# daughter-pots2_1.net
KiCad netlist of a schematic drawn in EAGLE
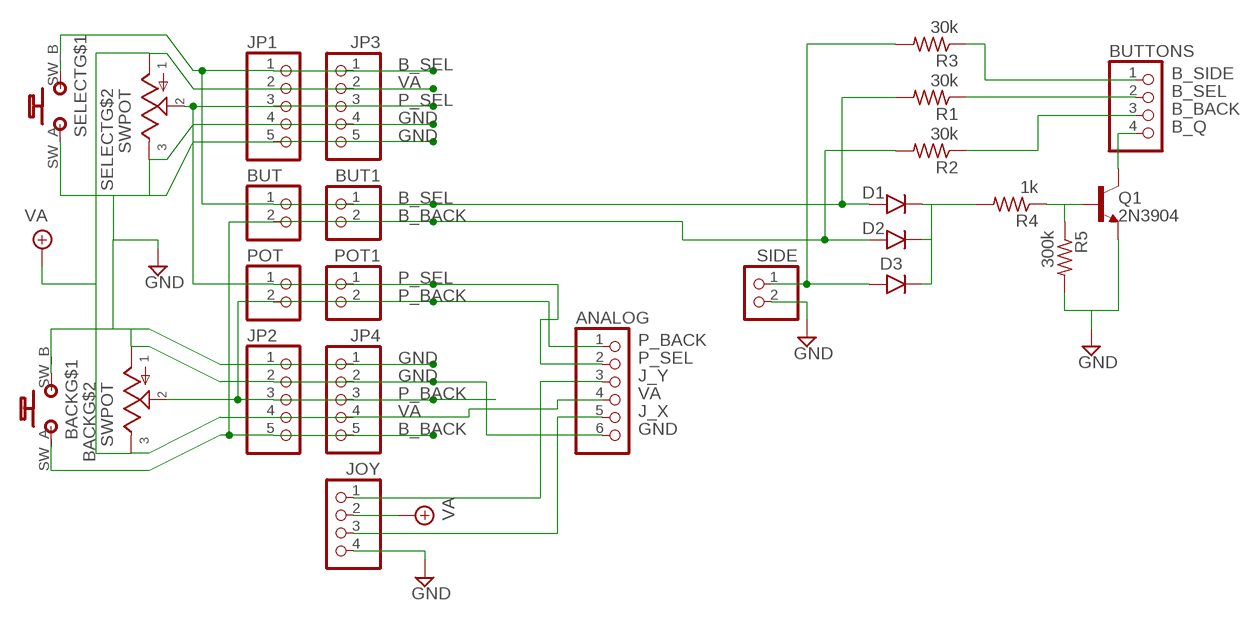
[diagram p0: schematic, sheet 1]

(export (version "E")
  (design (tool "Eeschema 10.0.6"))
  (components
    (comp (ref "ANALOG")
      (value "PINHD-1X6")
      (footprint "eagle-import:1X06")
      (libsource (lib "eagle-import") (part "PINHD-1X6"))
    )
    (comp (ref "BACK")
      (value "SWPOT")
      (footprint "eagle-import:SWPOT")
      (libsource (lib "eagle-import") (part "SWPOT"))
    )
    (comp (ref "BUT")
      (value "PINHD-1X2")
      (footprint "eagle-import:1X02")
      (libsource (lib "eagle-import") (part "PINHD-1X2"))
    )
    (comp (ref "BUT1")
      (value "PINHD-1X2")
      (footprint "eagle-import:1X02")
      (libsource (lib "eagle-import") (part "PINHD-1X2"))
    )
    (comp (ref "BUTTONS")
      (value "PINHD-1X4")
      (footprint "eagle-import:1X04")
      (libsource (lib "eagle-import") (part "PINHD-1X4"))
    )
    (comp (ref "D1")
      (value "1N4148-3")
      (footprint "eagle-import:DO35-3")
      (libsource (lib "eagle-import") (part "1N4148-3"))
    )
    (comp (ref "D2")
      (value "1N4148-2")
      (footprint "eagle-import:DO35-2")
      (libsource (lib "eagle-import") (part "1N4148-2"))
    )
    (comp (ref "D3")
      (value "1N4148-4")
      (footprint "eagle-import:DO35-4")
      (libsource (lib "eagle-import") (part "1N4148-4"))
    )
    (comp (ref "JOY")
      (value "PINHD-1X4")
      (footprint "eagle-import:1X04")
      (libsource (lib "eagle-import") (part "PINHD-1X4"))
    )
    (comp (ref "JP1")
      (value "PINHD-1X5")
      (footprint "eagle-import:1X05")
      (libsource (lib "eagle-import") (part "PINHD-1X5"))
    )
    (comp (ref "JP2")
      (value "PINHD-1X5")
      (footprint "eagle-import:1X05")
      (libsource (lib "eagle-import") (part "PINHD-1X5"))
    )
    (comp (ref "JP3")
      (value "PINHD-1X5")
      (footprint "eagle-import:1X05")
      (libsource (lib "eagle-import") (part "PINHD-1X5"))
    )
    (comp (ref "JP4")
      (value "PINHD-1X5")
      (footprint "eagle-import:1X05")
      (libsource (lib "eagle-import") (part "PINHD-1X5"))
    )
    (comp (ref "POT")
      (value "PINHD-1X2")
      (footprint "eagle-import:1X02")
      (libsource (lib "eagle-import") (part "PINHD-1X2"))
    )
    (comp (ref "POT1")
      (value "PINHD-1X2")
      (footprint "eagle-import:1X02")
      (libsource (lib "eagle-import") (part "PINHD-1X2"))
    )
    (comp (ref "Q1")
      (value "2N3904")
      (footprint "eagle-import:TO92-")
      (libsource (lib "eagle-import") (part "2N3904"))
    )
    (comp (ref "R1")
      (value "30k")
      (footprint "eagle-import:R0207_3")
      (libsource (lib "eagle-import") (part "6MM.3"))
    )
    (comp (ref "R2")
      (value "30k")
      (footprint "eagle-import:R0207_3")
      (libsource (lib "eagle-import") (part "6MM.3"))
    )
    (comp (ref "R3")
      (value "30k")
      (footprint "eagle-import:R0207_3")
      (libsource (lib "eagle-import") (part "6MM.3"))
    )
    (comp (ref "R4")
      (value "1k")
      (footprint "eagle-import:R0207_3")
      (libsource (lib "eagle-import") (part "6MM.3"))
    )
    (comp (ref "R5")
      (value "300k")
      (footprint "eagle-import:R0207_1V")
      (libsource (lib "eagle-import") (part "6MM.1"))
    )
    (comp (ref "SELECT")
      (value "SWPOT")
      (footprint "eagle-import:SWPOT")
      (libsource (lib "eagle-import") (part "SWPOT"))
    )
    (comp (ref "SIDE")
      (value "PINHD-1X2")
      (footprint "eagle-import:1X02")
      (libsource (lib "eagle-import") (part "PINHD-1X2"))
    )
  )
  (nets
    (net (code "1") (name "/B_BACK") (class "Default")
      (node (ref "BACK") (pin "SW_A") (pinfunction "B_A_SW_A") (pintype "passive"))
      (node (ref "BUT") (pin "2") (pinfunction "2_2") (pintype "passive"))
      (node (ref "BUT1") (pin "2") (pinfunction "2_2") (pintype "passive"))
      (node (ref "D2") (pin "A") (pinfunction "A_A") (pintype "passive"))
      (node (ref "JP2") (pin "5") (pinfunction "5_5") (pintype "passive"))
      (node (ref "JP4") (pin "5") (pinfunction "5_5") (pintype "passive"))
      (node (ref "R2") (pin "2") (pinfunction "2_2") (pintype "passive"))
    )
    (net (code "2") (name "/B_Q") (class "Default")
      (node (ref "BUTTONS") (pin "4") (pinfunction "4_4") (pintype "passive"))
      (node (ref "Q1") (pin "1") (pinfunction "C_1") (pintype "passive"))
    )
    (net (code "3") (name "/B_SEL") (class "Default")
      (node (ref "BUT") (pin "1") (pinfunction "1_1") (pintype "passive"))
      (node (ref "BUT1") (pin "1") (pinfunction "1_1") (pintype "passive"))
      (node (ref "D1") (pin "A") (pinfunction "A_A") (pintype "passive"))
      (node (ref "JP1") (pin "1") (pinfunction "1_1") (pintype "passive"))
      (node (ref "JP3") (pin "1") (pinfunction "1_1") (pintype "passive"))
      (node (ref "R1") (pin "2") (pinfunction "2_2") (pintype "passive"))
      (node (ref "SELECT") (pin "SW_B") (pinfunction "B_B_SW_B") (pintype "passive"))
    )
    (net (code "4") (name "/B_SIDE") (class "Default")
      (node (ref "D3") (pin "A") (pinfunction "A_A") (pintype "passive"))
      (node (ref "R3") (pin "2") (pinfunction "2_2") (pintype "passive"))
      (node (ref "SIDE") (pin "1") (pinfunction "1_1") (pintype "passive"))
    )
    (net (code "5") (name "/J_X") (class "Default")
      (node (ref "ANALOG") (pin "5") (pinfunction "5_5") (pintype "passive"))
      (node (ref "JOY") (pin "3") (pinfunction "3_3") (pintype "passive"))
    )
    (net (code "6") (name "/J_Y") (class "Default")
      (node (ref "ANALOG") (pin "3") (pinfunction "3_3") (pintype "passive"))
      (node (ref "JOY") (pin "1") (pinfunction "1_1") (pintype "passive"))
    )
    (net (code "7") (name "/P_BACK") (class "Default")
      (node (ref "ANALOG") (pin "1") (pinfunction "1_1") (pintype "passive"))
      (node (ref "BACK") (pin "POT_W") (pinfunction "POT_W_POT_W") (pintype "passive"))
      (node (ref "JP2") (pin "3") (pinfunction "3_3") (pintype "passive"))
      (node (ref "JP4") (pin "3") (pinfunction "3_3") (pintype "passive"))
      (node (ref "POT") (pin "2") (pinfunction "2_2") (pintype "passive"))
      (node (ref "POT1") (pin "2") (pinfunction "2_2") (pintype "passive"))
    )
    (net (code "8") (name "/P_SEL") (class "Default")
      (node (ref "ANALOG") (pin "2") (pinfunction "2_2") (pintype "passive"))
      (node (ref "JP1") (pin "3") (pinfunction "3_3") (pintype "passive"))
      (node (ref "JP3") (pin "3") (pinfunction "3_3") (pintype "passive"))
      (node (ref "POT") (pin "1") (pinfunction "1_1") (pintype "passive"))
      (node (ref "POT1") (pin "1") (pinfunction "1_1") (pintype "passive"))
      (node (ref "SELECT") (pin "POT_W") (pinfunction "POT_W_POT_W") (pintype "passive"))
    )
    (net (code "9") (name "GND") (class "Default")
      (node (ref "ANALOG") (pin "6") (pinfunction "6_6") (pintype "passive"))
      (node (ref "BACK") (pin "POT_B") (pinfunction "POT_B_POT_B") (pintype "passive"))
      (node (ref "BACK") (pin "SW_B") (pinfunction "B_B_SW_B") (pintype "passive"))
      (node (ref "JOY") (pin "4") (pinfunction "4_4") (pintype "passive"))
      (node (ref "JP1") (pin "4") (pinfunction "4_4") (pintype "passive"))
      (node (ref "JP1") (pin "5") (pinfunction "5_5") (pintype "passive"))
      (node (ref "JP2") (pin "1") (pinfunction "1_1") (pintype "passive"))
      (node (ref "JP2") (pin "2") (pinfunction "2_2") (pintype "passive"))
      (node (ref "JP3") (pin "4") (pinfunction "4_4") (pintype "passive"))
      (node (ref "JP3") (pin "5") (pinfunction "5_5") (pintype "passive"))
      (node (ref "JP4") (pin "1") (pinfunction "1_1") (pintype "passive"))
      (node (ref "JP4") (pin "2") (pinfunction "2_2") (pintype "passive"))
      (node (ref "Q1") (pin "3") (pinfunction "E_3") (pintype "passive"))
      (node (ref "R5") (pin "2") (pinfunction "2_2") (pintype "passive"))
      (node (ref "SELECT") (pin "POT_A") (pinfunction "POT_A_POT_A") (pintype "passive"))
      (node (ref "SELECT") (pin "SW_A") (pinfunction "B_A_SW_A") (pintype "passive"))
      (node (ref "SIDE") (pin "2") (pinfunction "2_2") (pintype "passive"))
    )
    (net (code "10") (name "Net-(BUTTONS-Pad1)") (class "Default")
      (node (ref "BUTTONS") (pin "1") (pinfunction "1_1") (pintype "passive"))
      (node (ref "R3") (pin "1") (pinfunction "1_1") (pintype "passive"))
    )
    (net (code "11") (name "Net-(BUTTONS-Pad2)") (class "Default")
      (node (ref "BUTTONS") (pin "2") (pinfunction "2_2") (pintype "passive"))
      (node (ref "R1") (pin "1") (pinfunction "1_1") (pintype "passive"))
    )
    (net (code "12") (name "Net-(BUTTONS-Pad3)") (class "Default")
      (node (ref "BUTTONS") (pin "3") (pinfunction "3_3") (pintype "passive"))
      (node (ref "R2") (pin "1") (pinfunction "1_1") (pintype "passive"))
    )
    (net (code "13") (name "Net-(D1-PadC)") (class "Default")
      (node (ref "D1") (pin "C") (pinfunction "C_C") (pintype "passive"))
      (node (ref "D2") (pin "C") (pinfunction "C_C") (pintype "passive"))
      (node (ref "D3") (pin "C") (pinfunction "C_C") (pintype "passive"))
      (node (ref "R4") (pin "2") (pinfunction "2_2") (pintype "passive"))
    )
    (net (code "14") (name "Net-(Q1-B)") (class "Default")
      (node (ref "Q1") (pin "2") (pinfunction "B_2") (pintype "passive"))
      (node (ref "R4") (pin "1") (pinfunction "1_1") (pintype "passive"))
      (node (ref "R5") (pin "1") (pinfunction "1_1") (pintype "passive"))
    )
    (net (code "15") (name "VA") (class "Default")
      (node (ref "ANALOG") (pin "4") (pinfunction "4_4") (pintype "passive"))
      (node (ref "BACK") (pin "POT_A") (pinfunction "POT_A_POT_A") (pintype "passive"))
      (node (ref "JOY") (pin "2") (pinfunction "2_2") (pintype "passive"))
      (node (ref "JP1") (pin "2") (pinfunction "2_2") (pintype "passive"))
      (node (ref "JP2") (pin "4") (pinfunction "4_4") (pintype "passive"))
      (node (ref "JP3") (pin "2") (pinfunction "2_2") (pintype "passive"))
      (node (ref "JP4") (pin "4") (pinfunction "4_4") (pintype "passive"))
      (node (ref "SELECT") (pin "POT_B") (pinfunction "POT_B_POT_B") (pintype "passive"))
    )
  )
)
